# handheld_circuits.net
KiCad netlist of a schematic drawn in Altium Designer
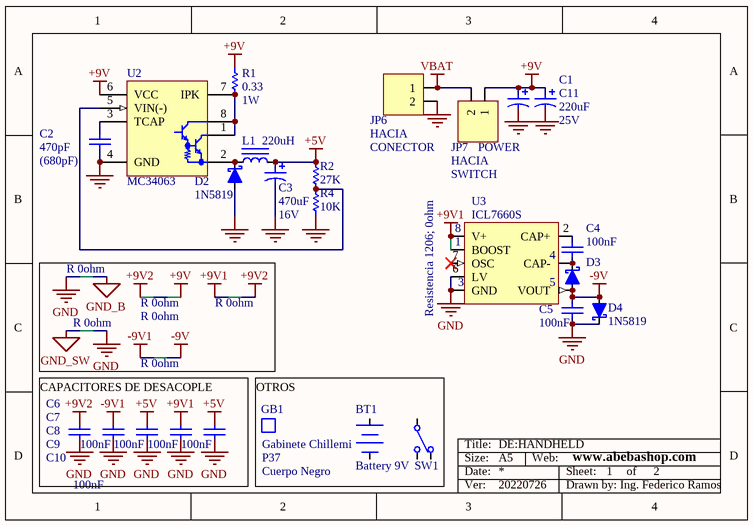
[diagram p0: handheld_circuits.SchDoc]

(export (version "E")
  (design (tool "Eeschema 10.0.6"))
  (components
    (comp (ref "BT1") (value "Battery 9V") (footprint "BAT_9V") (libsource (lib "FEDE") (part "Battery 9V")))
    (comp (ref "C1")
      (value "Cap Pol")
      (footprint "C_EL_8X11-5")
      (description "Capacitor Polarizado")
      (libsource (lib "FEDE") (part "Cap Pol"))
    )
    (comp (ref "C2")
      (value "470pF")
      (footprint "c1206")
      (description "Capacitor")
      (fields
        (field (name "VOLTAGE") "50V")
        (field (name "TECHNOLOGY") "(680pF)")
        (field (name "Comment") "Cap")
      )
      (libsource (lib "FEDE") (part "Cap"))
    )
    (comp (ref "C3")
      (value "470uF")
      (footprint "C_EL_6-3X11")
      (description "Capacitor Polarizado")
      (fields (field (name "VOLTAJE") "16V") (field (name "Comment") "Cap Pol"))
      (libsource (lib "FEDE") (part "Cap Pol"))
    )
    (comp (ref "C4")
      (value "100nF")
      (footprint "c1206")
      (description "Capacitor")
      (fields (field (name "VOLTAGE") "50V") (field (name "Comment") "Cap"))
      (libsource (lib "FEDE") (part "Cap"))
    )
    (comp (ref "C5")
      (value "100nF")
      (footprint "c1206")
      (description "Capacitor")
      (fields (field (name "VOLTAGE") "50V") (field (name "Comment") "Cap"))
      (libsource (lib "FEDE") (part "Cap"))
    )
    (comp (ref "C6")
      (value "100nF")
      (footprint "c1206")
      (description "Capacitor")
      (fields (field (name "VOLTAGE") "50V") (field (name "Comment") "Cap"))
      (libsource (lib "FEDE") (part "Cap"))
    )
    (comp (ref "C7")
      (value "100nF")
      (footprint "c1206")
      (description "Capacitor")
      (fields (field (name "VOLTAGE") "50V") (field (name "Comment") "Cap"))
      (libsource (lib "FEDE") (part "Cap"))
    )
    (comp (ref "C8")
      (value "100nF")
      (footprint "c1206")
      (description "Capacitor")
      (fields (field (name "VOLTAGE") "50V") (field (name "Comment") "Cap"))
      (libsource (lib "FEDE") (part "Cap"))
    )
    (comp (ref "C9")
      (value "100nF")
      (footprint "c1206")
      (description "Capacitor")
      (fields (field (name "VOLTAGE") "50V") (field (name "Comment") "Cap"))
      (libsource (lib "FEDE") (part "Cap"))
    )
    (comp (ref "C10")
      (value "100nF")
      (footprint "c1206")
      (description "Capacitor")
      (fields (field (name "VOLTAGE") "50V") (field (name "Comment") "Cap"))
      (libsource (lib "FEDE") (part "Cap"))
    )
    (comp (ref "C11")
      (value "220uF")
      (footprint "C_EL_8X11-5")
      (description "Capacitor Polarizado")
      (fields (field (name "VOLTAJE") "25V") (field (name "Comment") "Cap Pol"))
      (libsource (lib "FEDE") (part "Cap Pol"))
    )
    (comp (ref "D2")
      (value "1N5819")
      (footprint "d_do41")
      (description "Schottky Diode 1A 40V")
      (libsource (lib "FEDE") (part "1N5819"))
    )
    (comp (ref "D3")
      (value "1N5819")
      (footprint "d_do41")
      (description "Schottky Diode 1A 40V")
      (libsource (lib "FEDE") (part "1N5819"))
    )
    (comp (ref "D4")
      (value "1N5819")
      (footprint "d_do41")
      (description "Schottky Diode 1A 40V")
      (libsource (lib "FEDE") (part "1N5819"))
    )
    (comp (ref "GB1")
      (value "Gabinete Chillemi")
      (footprint "PLA_GAB_HAND_HALF")
      (fields (field (name "CODIGO CHILLEMI") "P37") (field (name "DOLARES CHILLEMI") "Cuerpo Negro"))
      (libsource (lib "FEDE") (part "Gabinete Chillemi P37; Cuerpo Negro"))
    )
    (comp (ref "JP6")
      (value "HACIA")
      (footprint "CONPOL2X1")
      (description "Header 2x1")
      (fields (field (name "PRICE") "CONECTOR"))
      (libsource (lib "FEDE") (part "Header2x1"))
    )
    (comp (ref "JP7")
      (value "XY128V-A2P")
      (footprint "CONPOL2X1")
      (description "Bornera Tornillos 2x1; Altura = 13.8mm")
      (fields
        (field (name "CODIGO ELEMON") "HACIA")
        (field (name "DOLARES ELEMON") "POWER")
        (field (name "XXX") "SWITCH")
      )
      (libsource (lib "FEDE") (part "Bornera Tornillos 2x1; Altura = 13.8mm"))
    )
    (comp (ref "L1")
      (value "220uH")
      (footprint "L_10X12")
      (description "Inductor")
      (libsource (lib "FEDE") (part "Inductor"))
    )
    (comp (ref "R1")
      (value "Resistencia 1W; 100Kohm")
      (footprint "RES300TH")
      (fields (field (name "RESISTENCIA") "0.33") (field (name "ALTIUM_UNNAMED_1") "1W"))
      (libsource (lib "FEDE") (part "Resistencia 1W; 100Kohm"))
    )
    (comp (ref "R2")
      (value "Resistencia 1206; 1Kohm")
      (footprint "R1206")
      (fields (field (name "RESISTENCIA") "27K"))
      (libsource (lib "FEDE") (part "Resistencia 1206; 1Kohm"))
    )
    (comp (ref "R4")
      (value "Resistencia 1206; 1Kohm")
      (footprint "R1206")
      (fields (field (name "RESISTENCIA") "10K"))
      (libsource (lib "FEDE") (part "Resistencia 1206; 1Kohm"))
    )
    (comp (ref "R15")
      (value "Resistencia 1206; 0ohm")
      (footprint "R1206")
      (libsource (lib "FEDE") (part "Resistencia 1206; 0ohm"))
    )
    (comp (ref "R16")
      (value "R 0ohm")
      (footprint "R1206")
      (description "Resistencia 1206; 0ohm")
      (libsource (lib "FEDE") (part "Resistencia 1206; 0ohm"))
    )
    (comp (ref "R19")
      (value "R 0ohm")
      (footprint "R1206")
      (description "Resistencia 1206; 0ohm")
      (libsource (lib "FEDE") (part "Resistencia 1206; 0ohm"))
    )
    (comp (ref "R21")
      (value "R 0ohm")
      (footprint "R1206")
      (description "Resistencia 1206; 0ohm")
      (libsource (lib "FEDE") (part "Resistencia 1206; 0ohm"))
    )
    (comp (ref "R25")
      (value "R 0ohm")
      (footprint "R1206")
      (description "Resistencia 1206; 0ohm")
      (libsource (lib "FEDE") (part "Resistencia 1206; 0ohm"))
    )
    (comp (ref "R26")
      (value "R 0ohm")
      (footprint "R1206")
      (description "Resistencia 1206; 0ohm")
      (libsource (lib "FEDE") (part "Resistencia 1206; 0ohm"))
    )
    (comp (ref "R28")
      (value "R 0ohm")
      (footprint "R1206")
      (description "Resistencia 1206; 0ohm")
      (libsource (lib "FEDE") (part "Resistencia 1206; 0ohm"))
    )
    (comp (ref "SW1")
      (value "Tecla (sin pads)")
      (footprint "SW_TECLA_NO_PADS")
      (libsource (lib "FEDE") (part "Tecla (sin pads)"))
    )
    (comp (ref "U2")
      (value "MC34063")
      (footprint "dip8z")
      (description "DC-to-DC Converter Control Circuit")
      (libsource (lib "FEDE") (part "MC34063"))
    )
    (comp (ref "U3")
      (value "ICL7660S")
      (footprint "DIP8Z")
      (description "Switched Capacitor Voltage Converter")
      (libsource (lib "FEDE") (part "ICL7660S"))
    )
  )
  (nets
    (net (code "1") (name "+5V") (class "Default")
      (node (ref "C10") (pin "2") (pinfunction "2_2") (pintype "passive"))
      (node (ref "C3") (pin "1") (pinfunction "1_1") (pintype "passive"))
      (node (ref "C8") (pin "2") (pinfunction "2_2") (pintype "passive"))
      (node (ref "L1") (pin "2") (pinfunction "2_2") (pintype "passive"))
      (node (ref "R2") (pin "1") (pinfunction "1_1") (pintype "passive"))
    )
    (net (code "2") (name "+9V") (class "Default")
      (node (ref "C1") (pin "1") (pinfunction "1_1") (pintype "passive"))
      (node (ref "C11") (pin "1") (pinfunction "1_1") (pintype "passive"))
      (node (ref "JP7") (pin "1") (pinfunction "1_1") (pintype "passive"))
      (node (ref "R1") (pin "2") (pinfunction "2_2") (pintype "passive"))
      (node (ref "R26") (pin "1") (pinfunction "1_1") (pintype "passive"))
      (node (ref "U2") (pin "6") (pinfunction "VCC_6") (pintype "power_in"))
    )
    (net (code "3") (name "+9V1") (class "Default")
      (node (ref "C9") (pin "2") (pinfunction "2_2") (pintype "passive"))
      (node (ref "R15") (pin "2") (pinfunction "2_2") (pintype "passive"))
      (node (ref "R16") (pin "2") (pinfunction "2_2") (pintype "passive"))
      (node (ref "U3") (pin "8") (pinfunction "V+_8") (pintype "power_in"))
    )
    (net (code "4") (name "+9V2") (class "Default")
      (node (ref "C6") (pin "2") (pinfunction "2_2") (pintype "passive"))
      (node (ref "R16") (pin "1") (pinfunction "1_1") (pintype "passive"))
      (node (ref "R25") (pin "2") (pinfunction "2_2") (pintype "passive"))
    )
    (net (code "5") (name "-9V") (class "Default")
      (node (ref "C5") (pin "2") (pinfunction "2_2") (pintype "passive"))
      (node (ref "D3") (pin "1") (pinfunction "A_1") (pintype "passive"))
      (node (ref "D4") (pin "1") (pinfunction "A_1") (pintype "passive"))
      (node (ref "R28") (pin "1") (pinfunction "1_1") (pintype "passive"))
      (node (ref "U3") (pin "5") (pinfunction "VOUT_5") (pintype "output"))
    )
    (net (code "6") (name "-9V1") (class "Default")
      (node (ref "C7") (pin "2") (pinfunction "2_2") (pintype "passive"))
      (node (ref "R28") (pin "2") (pinfunction "2_2") (pintype "passive"))
    )
    (net (code "7") (name "GND") (class "Default")
      (node (ref "C1") (pin "2") (pinfunction "2_2") (pintype "passive"))
      (node (ref "C10") (pin "1") (pinfunction "1_1") (pintype "passive"))
      (node (ref "C11") (pin "2") (pinfunction "2_2") (pintype "passive"))
      (node (ref "C2") (pin "1") (pinfunction "1_1") (pintype "passive"))
      (node (ref "C3") (pin "2") (pinfunction "2_2") (pintype "passive"))
      (node (ref "C5") (pin "1") (pinfunction "1_1") (pintype "passive"))
      (node (ref "C6") (pin "1") (pinfunction "1_1") (pintype "passive"))
      (node (ref "C7") (pin "1") (pinfunction "1_1") (pintype "passive"))
      (node (ref "C8") (pin "1") (pinfunction "1_1") (pintype "passive"))
      (node (ref "C9") (pin "1") (pinfunction "1_1") (pintype "passive"))
      (node (ref "D2") (pin "1") (pinfunction "A_1") (pintype "passive"))
      (node (ref "D4") (pin "2") (pinfunction "K_2") (pintype "passive"))
      (node (ref "JP6") (pin "2") (pinfunction "2_2") (pintype "passive"))
      (node (ref "R19") (pin "2") (pinfunction "2_2") (pintype "passive"))
      (node (ref "R21") (pin "1") (pinfunction "1_1") (pintype "passive"))
      (node (ref "R4") (pin "1") (pinfunction "1_1") (pintype "passive"))
      (node (ref "U2") (pin "4") (pinfunction "GND_4") (pintype "power_in"))
      (node (ref "U3") (pin "3") (pinfunction "GND_3") (pintype "power_in"))
      (node (ref "U3") (pin "6") (pinfunction "LV_6") (pintype "passive"))
    )
    (net (code "8") (name "GND_B") (class "Default")
      (node (ref "R19") (pin "1") (pinfunction "1_1") (pintype "passive"))
    )
    (net (code "9") (name "GND_SW") (class "Default")
      (node (ref "R21") (pin "2") (pinfunction "2_2") (pintype "passive"))
    )
    (net (code "10") (name "Net-(D2-K)") (class "Default")
      (node (ref "D2") (pin "2") (pinfunction "K_2") (pintype "passive"))
      (node (ref "L1") (pin "1") (pinfunction "1_1") (pintype "passive"))
      (node (ref "U2") (pin "2") (pinfunction "SWE_2") (pintype "open_emitter"))
    )
    (net (code "11") (name "Net-(D3-K)") (class "Default")
      (node (ref "C4") (pin "1") (pinfunction "1_1") (pintype "passive"))
      (node (ref "D3") (pin "2") (pinfunction "K_2") (pintype "passive"))
      (node (ref "U3") (pin "4") (pinfunction "CAP-_4") (pintype "passive"))
    )
    (net (code "12") (name "Net-(R25-Pad1)") (class "Default")
      (node (ref "R25") (pin "1") (pinfunction "1_1") (pintype "passive"))
      (node (ref "R26") (pin "2") (pinfunction "2_2") (pintype "passive"))
    )
    (net (code "13") (name "Net-(U2-DRVC)") (class "Default")
      (node (ref "R1") (pin "1") (pinfunction "1_1") (pintype "passive"))
      (node (ref "U2") (pin "1") (pinfunction "SWC_1") (pintype "open_collector"))
      (node (ref "U2") (pin "7") (pinfunction "IPK_7") (pintype "passive"))
      (node (ref "U2") (pin "8") (pinfunction "DRVC_8") (pintype "open_collector"))
    )
    (net (code "14") (name "Net-(U2-TCAP)") (class "Default")
      (node (ref "C2") (pin "2") (pinfunction "2_2") (pintype "passive"))
      (node (ref "U2") (pin "3") (pinfunction "TCAP_3") (pintype "passive"))
    )
    (net (code "15") (name "Net-(U2-VIN(-))") (class "Default")
      (node (ref "R2") (pin "2") (pinfunction "2_2") (pintype "passive"))
      (node (ref "R4") (pin "2") (pinfunction "2_2") (pintype "passive"))
      (node (ref "U2") (pin "5") (pinfunction "VIN(-)_5") (pintype "input"))
    )
    (net (code "16") (name "Net-(U3-BOOST)") (class "Default")
      (node (ref "R15") (pin "1") (pinfunction "1_1") (pintype "passive"))
      (node (ref "U3") (pin "1") (pinfunction "BOOST_1") (pintype "passive"))
    )
    (net (code "17") (name "Net-(U3-CAP+)") (class "Default")
      (node (ref "C4") (pin "2") (pinfunction "2_2") (pintype "passive"))
      (node (ref "U3") (pin "2") (pinfunction "CAP+_2") (pintype "passive"))
    )
    (net (code "18") (name "VBAT") (class "Default")
      (node (ref "JP6") (pin "1") (pinfunction "1_1") (pintype "passive"))
      (node (ref "JP7") (pin "2") (pinfunction "2_2") (pintype "passive"))
    )
    (net (code "19") (name "unconnected-(U3-OSC-Pad7)") (class "Default")
      (node (ref "U3") (pin "7") (pinfunction "OSC_7") (pintype "input+no_connect"))
    )
  )
)
